# Integrator.net
KiCad netlist of a schematic drawn in EAGLE
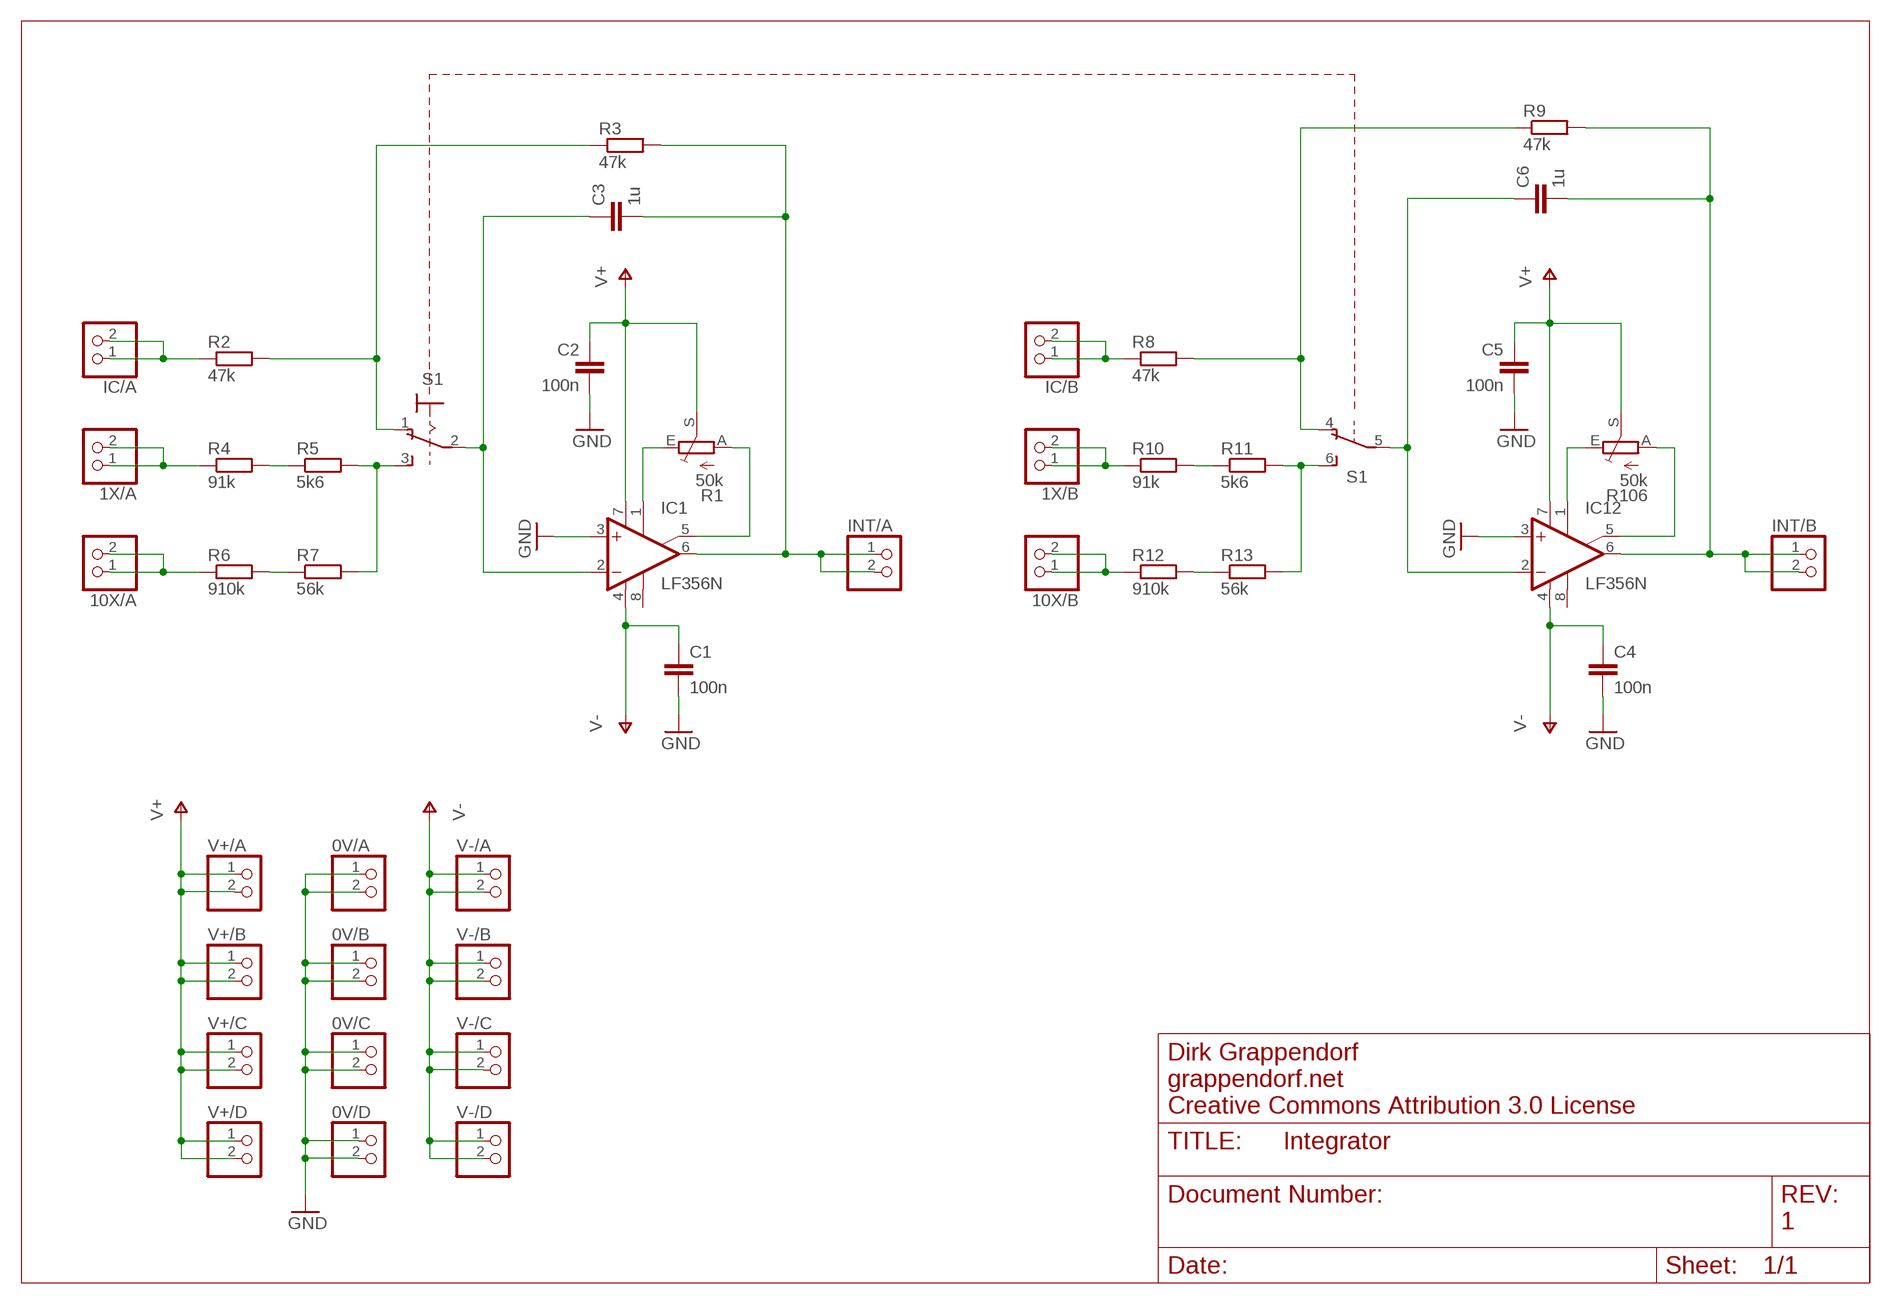
[diagram p0: schematic, sheet 1]

(export (version "E")
  (design (tool "Eeschema 10.0.6"))
  (components
    (comp (ref "0V/A")
      (value "PINHD-1X2")
      (footprint "eagle-import:1X02")
      (libsource (lib "eagle-import") (part "PINHD-1X2"))
    )
    (comp (ref "0V/B")
      (value "PINHD-1X2")
      (footprint "eagle-import:1X02")
      (libsource (lib "eagle-import") (part "PINHD-1X2"))
    )
    (comp (ref "0V/C")
      (value "PINHD-1X2")
      (footprint "eagle-import:1X02")
      (libsource (lib "eagle-import") (part "PINHD-1X2"))
    )
    (comp (ref "0V/D")
      (value "PINHD-1X2")
      (footprint "eagle-import:1X02")
      (libsource (lib "eagle-import") (part "PINHD-1X2"))
    )
    (comp (ref "1X/A")
      (value "PINHD-1X2")
      (footprint "eagle-import:1X02")
      (libsource (lib "eagle-import") (part "PINHD-1X2"))
    )
    (comp (ref "1X/B")
      (value "PINHD-1X2")
      (footprint "eagle-import:1X02")
      (libsource (lib "eagle-import") (part "PINHD-1X2"))
    )
    (comp (ref "10X/A")
      (value "PINHD-1X2")
      (footprint "eagle-import:1X02")
      (libsource (lib "eagle-import") (part "PINHD-1X2"))
    )
    (comp (ref "10X/B")
      (value "PINHD-1X2")
      (footprint "eagle-import:1X02")
      (libsource (lib "eagle-import") (part "PINHD-1X2"))
    )
    (comp (ref "C1")
      (value "100n")
      (footprint "eagle-import:C025-025X050")
      (libsource (lib "eagle-import") (part "C-EU025-025X050"))
    )
    (comp (ref "C2")
      (value "100n")
      (footprint "eagle-import:C025-025X050")
      (libsource (lib "eagle-import") (part "C-EU025-025X050"))
    )
    (comp (ref "C3")
      (value "1u")
      (footprint "eagle-import:C050-035X075")
      (libsource (lib "eagle-import") (part "C-EU050-035X075"))
    )
    (comp (ref "C4")
      (value "100n")
      (footprint "eagle-import:C025-025X050")
      (libsource (lib "eagle-import") (part "C-EU025-025X050"))
    )
    (comp (ref "C5")
      (value "100n")
      (footprint "eagle-import:C025-025X050")
      (libsource (lib "eagle-import") (part "C-EU025-025X050"))
    )
    (comp (ref "C6")
      (value "1u")
      (footprint "eagle-import:C050-035X075")
      (libsource (lib "eagle-import") (part "C-EU050-035X075"))
    )
    (comp (ref "IC/A")
      (value "PINHD-1X2")
      (footprint "eagle-import:1X02")
      (libsource (lib "eagle-import") (part "PINHD-1X2"))
    )
    (comp (ref "IC/B")
      (value "PINHD-1X2")
      (footprint "eagle-import:1X02")
      (libsource (lib "eagle-import") (part "PINHD-1X2"))
    )
    (comp (ref "IC1")
      (value "LF356N")
      (footprint "eagle-import:DIL08")
      (libsource (lib "eagle-import") (part "LF356N"))
    )
    (comp (ref "IC12")
      (value "LF356N")
      (footprint "eagle-import:DIL08")
      (libsource (lib "eagle-import") (part "LF356N"))
    )
    (comp (ref "INT/A")
      (value "PINHD-1X2")
      (footprint "eagle-import:1X02")
      (libsource (lib "eagle-import") (part "PINHD-1X2"))
    )
    (comp (ref "INT/B")
      (value "PINHD-1X2")
      (footprint "eagle-import:1X02")
      (libsource (lib "eagle-import") (part "PINHD-1X2"))
    )
    (comp (ref "R1")
      (value "50k")
      (footprint "eagle-import:LI15")
      (libsource (lib "eagle-import") (part "TRIM_EU-LI15"))
    )
    (comp (ref "R2")
      (value "47k")
      (footprint "eagle-import:0207_7")
      (libsource (lib "eagle-import") (part "R-EU_0207/7"))
    )
    (comp (ref "R3")
      (value "47k")
      (footprint "eagle-import:0207_7")
      (libsource (lib "eagle-import") (part "R-EU_0207/7"))
    )
    (comp (ref "R4")
      (value "91k")
      (footprint "eagle-import:0207_7")
      (libsource (lib "eagle-import") (part "R-EU_0207/7"))
    )
    (comp (ref "R5")
      (value "5k6")
      (footprint "eagle-import:0207_7")
      (libsource (lib "eagle-import") (part "R-EU_0207/7"))
    )
    (comp (ref "R6")
      (value "910k")
      (footprint "eagle-import:0207_7")
      (libsource (lib "eagle-import") (part "R-EU_0207/7"))
    )
    (comp (ref "R7")
      (value "56k")
      (footprint "eagle-import:0207_7")
      (libsource (lib "eagle-import") (part "R-EU_0207/7"))
    )
    (comp (ref "R8")
      (value "47k")
      (footprint "eagle-import:0207_7")
      (libsource (lib "eagle-import") (part "R-EU_0207/7"))
    )
    (comp (ref "R9")
      (value "47k")
      (footprint "eagle-import:0207_7")
      (libsource (lib "eagle-import") (part "R-EU_0207/7"))
    )
    (comp (ref "R10")
      (value "91k")
      (footprint "eagle-import:0207_7")
      (libsource (lib "eagle-import") (part "R-EU_0207/7"))
    )
    (comp (ref "R11")
      (value "5k6")
      (footprint "eagle-import:0207_7")
      (libsource (lib "eagle-import") (part "R-EU_0207/7"))
    )
    (comp (ref "R12")
      (value "910k")
      (footprint "eagle-import:0207_7")
      (libsource (lib "eagle-import") (part "R-EU_0207/7"))
    )
    (comp (ref "R13")
      (value "56k")
      (footprint "eagle-import:0207_7")
      (libsource (lib "eagle-import") (part "R-EU_0207/7"))
    )
    (comp (ref "R106")
      (value "50k")
      (footprint "eagle-import:LI15")
      (libsource (lib "eagle-import") (part "TRIM_EU-LI15"))
    )
    (comp (ref "S1")
      (value "REICHELT-MS_500H")
      (footprint "eagle-import:REICHELT-MS_500H")
      (libsource (lib "eagle-import") (part "REICHELT-MS_500H"))
    )
    (comp (ref "V+/A")
      (value "PINHD-1X2")
      (footprint "eagle-import:1X02")
      (libsource (lib "eagle-import") (part "PINHD-1X2"))
    )
    (comp (ref "V+/B")
      (value "PINHD-1X2")
      (footprint "eagle-import:1X02")
      (libsource (lib "eagle-import") (part "PINHD-1X2"))
    )
    (comp (ref "V+/C")
      (value "PINHD-1X2")
      (footprint "eagle-import:1X02")
      (libsource (lib "eagle-import") (part "PINHD-1X2"))
    )
    (comp (ref "V+/D")
      (value "PINHD-1X2")
      (footprint "eagle-import:1X02")
      (libsource (lib "eagle-import") (part "PINHD-1X2"))
    )
    (comp (ref "V-/A")
      (value "PINHD-1X2")
      (footprint "eagle-import:1X02")
      (libsource (lib "eagle-import") (part "PINHD-1X2"))
    )
    (comp (ref "V-/B")
      (value "PINHD-1X2")
      (footprint "eagle-import:1X02")
      (libsource (lib "eagle-import") (part "PINHD-1X2"))
    )
    (comp (ref "V-/C")
      (value "PINHD-1X2")
      (footprint "eagle-import:1X02")
      (libsource (lib "eagle-import") (part "PINHD-1X2"))
    )
    (comp (ref "V-/D")
      (value "PINHD-1X2")
      (footprint "eagle-import:1X02")
      (libsource (lib "eagle-import") (part "PINHD-1X2"))
    )
  )
  (nets
    (net (code "1") (name "GND") (class "Default")
      (node (ref "0V/A") (pin "1") (pinfunction "1_1") (pintype "passive"))
      (node (ref "0V/A") (pin "2") (pinfunction "2_2") (pintype "passive"))
      (node (ref "0V/B") (pin "1") (pinfunction "1_1") (pintype "passive"))
      (node (ref "0V/B") (pin "2") (pinfunction "2_2") (pintype "passive"))
      (node (ref "0V/C") (pin "1") (pinfunction "1_1") (pintype "passive"))
      (node (ref "0V/C") (pin "2") (pinfunction "2_2") (pintype "passive"))
      (node (ref "0V/D") (pin "1") (pinfunction "1_1") (pintype "passive"))
      (node (ref "0V/D") (pin "2") (pinfunction "2_2") (pintype "passive"))
      (node (ref "C1") (pin "2") (pinfunction "2_2") (pintype "passive"))
      (node (ref "C2") (pin "2") (pinfunction "2_2") (pintype "passive"))
      (node (ref "C4") (pin "2") (pinfunction "2_2") (pintype "passive"))
      (node (ref "C5") (pin "2") (pinfunction "2_2") (pintype "passive"))
      (node (ref "IC1") (pin "3") (pinfunction "+IN_3") (pintype "input"))
      (node (ref "IC12") (pin "3") (pinfunction "+IN_3") (pintype "input"))
    )
    (net (code "2") (name "Net-(1X/A-Pad1)") (class "Default")
      (node (ref "1X/A") (pin "1") (pinfunction "1_1") (pintype "passive"))
      (node (ref "1X/A") (pin "2") (pinfunction "2_2") (pintype "passive"))
      (node (ref "R4") (pin "1") (pinfunction "1_1") (pintype "passive"))
    )
    (net (code "3") (name "Net-(1X/B-Pad1)") (class "Default")
      (node (ref "1X/B") (pin "1") (pinfunction "1_1") (pintype "passive"))
      (node (ref "1X/B") (pin "2") (pinfunction "2_2") (pintype "passive"))
      (node (ref "R10") (pin "1") (pinfunction "1_1") (pintype "passive"))
    )
    (net (code "4") (name "Net-(10X/A-Pad1)") (class "Default")
      (node (ref "10X/A") (pin "1") (pinfunction "1_1") (pintype "passive"))
      (node (ref "10X/A") (pin "2") (pinfunction "2_2") (pintype "passive"))
      (node (ref "R6") (pin "1") (pinfunction "1_1") (pintype "passive"))
    )
    (net (code "5") (name "Net-(10X/B-Pad1)") (class "Default")
      (node (ref "10X/B") (pin "1") (pinfunction "1_1") (pintype "passive"))
      (node (ref "10X/B") (pin "2") (pinfunction "2_2") (pintype "passive"))
      (node (ref "R12") (pin "1") (pinfunction "1_1") (pintype "passive"))
    )
    (net (code "6") (name "Net-(IC/A-Pad1)") (class "Default")
      (node (ref "IC/A") (pin "1") (pinfunction "1_1") (pintype "passive"))
      (node (ref "IC/A") (pin "2") (pinfunction "2_2") (pintype "passive"))
      (node (ref "R2") (pin "1") (pinfunction "1_1") (pintype "passive"))
    )
    (net (code "7") (name "Net-(IC/B-Pad1)") (class "Default")
      (node (ref "IC/B") (pin "1") (pinfunction "1_1") (pintype "passive"))
      (node (ref "IC/B") (pin "2") (pinfunction "2_2") (pintype "passive"))
      (node (ref "R8") (pin "1") (pinfunction "1_1") (pintype "passive"))
    )
    (net (code "8") (name "Net-(IC1--IN)") (class "Default")
      (node (ref "C3") (pin "1") (pinfunction "1_1") (pintype "passive"))
      (node (ref "IC1") (pin "2") (pinfunction "-IN_2") (pintype "input"))
      (node (ref "S1") (pin "2") (pinfunction "P_2") (pintype "passive"))
    )
    (net (code "9") (name "Net-(IC1-ON1)") (class "Default")
      (node (ref "IC1") (pin "1") (pinfunction "ON1_1") (pintype "passive"))
      (node (ref "R1") (pin "E") (pinfunction "E_E") (pintype "passive"))
    )
    (net (code "10") (name "Net-(IC1-ON2)") (class "Default")
      (node (ref "IC1") (pin "5") (pinfunction "ON2_5") (pintype "passive"))
      (node (ref "R1") (pin "A") (pinfunction "A_A") (pintype "passive"))
    )
    (net (code "11") (name "Net-(IC1-OUT)") (class "Default")
      (node (ref "C3") (pin "2") (pinfunction "2_2") (pintype "passive"))
      (node (ref "IC1") (pin "6") (pinfunction "OUT_6") (pintype "output"))
      (node (ref "INT/A") (pin "1") (pinfunction "1_1") (pintype "passive"))
      (node (ref "INT/A") (pin "2") (pinfunction "2_2") (pintype "passive"))
      (node (ref "R3") (pin "2") (pinfunction "2_2") (pintype "passive"))
    )
    (net (code "12") (name "Net-(IC12--IN)") (class "Default")
      (node (ref "C6") (pin "1") (pinfunction "1_1") (pintype "passive"))
      (node (ref "IC12") (pin "2") (pinfunction "-IN_2") (pintype "input"))
      (node (ref "S1") (pin "5") (pinfunction "P_5") (pintype "passive"))
    )
    (net (code "13") (name "Net-(IC12-ON1)") (class "Default")
      (node (ref "IC12") (pin "1") (pinfunction "ON1_1") (pintype "passive"))
      (node (ref "R106") (pin "E") (pinfunction "E_E") (pintype "passive"))
    )
    (net (code "14") (name "Net-(IC12-ON2)") (class "Default")
      (node (ref "IC12") (pin "5") (pinfunction "ON2_5") (pintype "passive"))
      (node (ref "R106") (pin "A") (pinfunction "A_A") (pintype "passive"))
    )
    (net (code "15") (name "Net-(IC12-OUT)") (class "Default")
      (node (ref "C6") (pin "2") (pinfunction "2_2") (pintype "passive"))
      (node (ref "IC12") (pin "6") (pinfunction "OUT_6") (pintype "output"))
      (node (ref "INT/B") (pin "1") (pinfunction "1_1") (pintype "passive"))
      (node (ref "INT/B") (pin "2") (pinfunction "2_2") (pintype "passive"))
      (node (ref "R9") (pin "2") (pinfunction "2_2") (pintype "passive"))
    )
    (net (code "16") (name "Net-(R4-Pad2)") (class "Default")
      (node (ref "R4") (pin "2") (pinfunction "2_2") (pintype "passive"))
      (node (ref "R5") (pin "1") (pinfunction "1_1") (pintype "passive"))
    )
    (net (code "17") (name "Net-(R6-Pad2)") (class "Default")
      (node (ref "R6") (pin "2") (pinfunction "2_2") (pintype "passive"))
      (node (ref "R7") (pin "1") (pinfunction "1_1") (pintype "passive"))
    )
    (net (code "18") (name "Net-(R10-Pad2)") (class "Default")
      (node (ref "R10") (pin "2") (pinfunction "2_2") (pintype "passive"))
      (node (ref "R11") (pin "1") (pinfunction "1_1") (pintype "passive"))
    )
    (net (code "19") (name "Net-(R12-Pad2)") (class "Default")
      (node (ref "R12") (pin "2") (pinfunction "2_2") (pintype "passive"))
      (node (ref "R13") (pin "1") (pinfunction "1_1") (pintype "passive"))
    )
    (net (code "20") (name "Net-(S1A-O)") (class "Default")
      (node (ref "R2") (pin "2") (pinfunction "2_2") (pintype "passive"))
      (node (ref "R3") (pin "1") (pinfunction "1_1") (pintype "passive"))
      (node (ref "S1") (pin "1") (pinfunction "O_1") (pintype "passive"))
    )
    (net (code "21") (name "Net-(S1A-S)") (class "Default")
      (node (ref "R5") (pin "2") (pinfunction "2_2") (pintype "passive"))
      (node (ref "R7") (pin "2") (pinfunction "2_2") (pintype "passive"))
      (node (ref "S1") (pin "3") (pinfunction "S_3") (pintype "passive"))
    )
    (net (code "22") (name "Net-(S1B-O)") (class "Default")
      (node (ref "R8") (pin "2") (pinfunction "2_2") (pintype "passive"))
      (node (ref "R9") (pin "1") (pinfunction "1_1") (pintype "passive"))
      (node (ref "S1") (pin "4") (pinfunction "O_4") (pintype "passive"))
    )
    (net (code "23") (name "Net-(S1B-S)") (class "Default")
      (node (ref "R11") (pin "2") (pinfunction "2_2") (pintype "passive"))
      (node (ref "R13") (pin "2") (pinfunction "2_2") (pintype "passive"))
      (node (ref "S1") (pin "6") (pinfunction "S_6") (pintype "passive"))
    )
    (net (code "24") (name "V+") (class "Default")
      (node (ref "C2") (pin "1") (pinfunction "1_1") (pintype "passive"))
      (node (ref "C5") (pin "1") (pinfunction "1_1") (pintype "passive"))
      (node (ref "IC1") (pin "7") (pinfunction "V+_7") (pintype "power_in"))
      (node (ref "IC12") (pin "7") (pinfunction "V+_7") (pintype "power_in"))
      (node (ref "R1") (pin "S") (pinfunction "S_S") (pintype "passive"))
      (node (ref "R106") (pin "S") (pinfunction "S_S") (pintype "passive"))
      (node (ref "V+/A") (pin "1") (pinfunction "1_1") (pintype "passive"))
      (node (ref "V+/A") (pin "2") (pinfunction "2_2") (pintype "passive"))
      (node (ref "V+/B") (pin "1") (pinfunction "1_1") (pintype "passive"))
      (node (ref "V+/B") (pin "2") (pinfunction "2_2") (pintype "passive"))
      (node (ref "V+/C") (pin "1") (pinfunction "1_1") (pintype "passive"))
      (node (ref "V+/C") (pin "2") (pinfunction "2_2") (pintype "passive"))
      (node (ref "V+/D") (pin "1") (pinfunction "1_1") (pintype "passive"))
      (node (ref "V+/D") (pin "2") (pinfunction "2_2") (pintype "passive"))
    )
    (net (code "25") (name "V-") (class "Default")
      (node (ref "C1") (pin "1") (pinfunction "1_1") (pintype "passive"))
      (node (ref "C4") (pin "1") (pinfunction "1_1") (pintype "passive"))
      (node (ref "IC1") (pin "4") (pinfunction "V-_4") (pintype "power_in"))
      (node (ref "IC12") (pin "4") (pinfunction "V-_4") (pintype "power_in"))
      (node (ref "V-/A") (pin "1") (pinfunction "1_1") (pintype "passive"))
      (node (ref "V-/A") (pin "2") (pinfunction "2_2") (pintype "passive"))
      (node (ref "V-/B") (pin "1") (pinfunction "1_1") (pintype "passive"))
      (node (ref "V-/B") (pin "2") (pinfunction "2_2") (pintype "passive"))
      (node (ref "V-/C") (pin "1") (pinfunction "1_1") (pintype "passive"))
      (node (ref "V-/C") (pin "2") (pinfunction "2_2") (pintype "passive"))
      (node (ref "V-/D") (pin "1") (pinfunction "1_1") (pintype "passive"))
      (node (ref "V-/D") (pin "2") (pinfunction "2_2") (pintype "passive"))
    )
    (net (code "26") (name "unconnected-(IC1-OPT-Pad8)") (class "Default")
      (node (ref "IC1") (pin "8") (pinfunction "OPT_8") (pintype "passive"))
    )
    (net (code "27") (name "unconnected-(IC12-OPT-Pad8)") (class "Default")
      (node (ref "IC12") (pin "8") (pinfunction "OPT_8") (pintype "passive"))
    )
  )
)
